# arduino.net
KiCad netlist of a schematic drawn in EAGLE
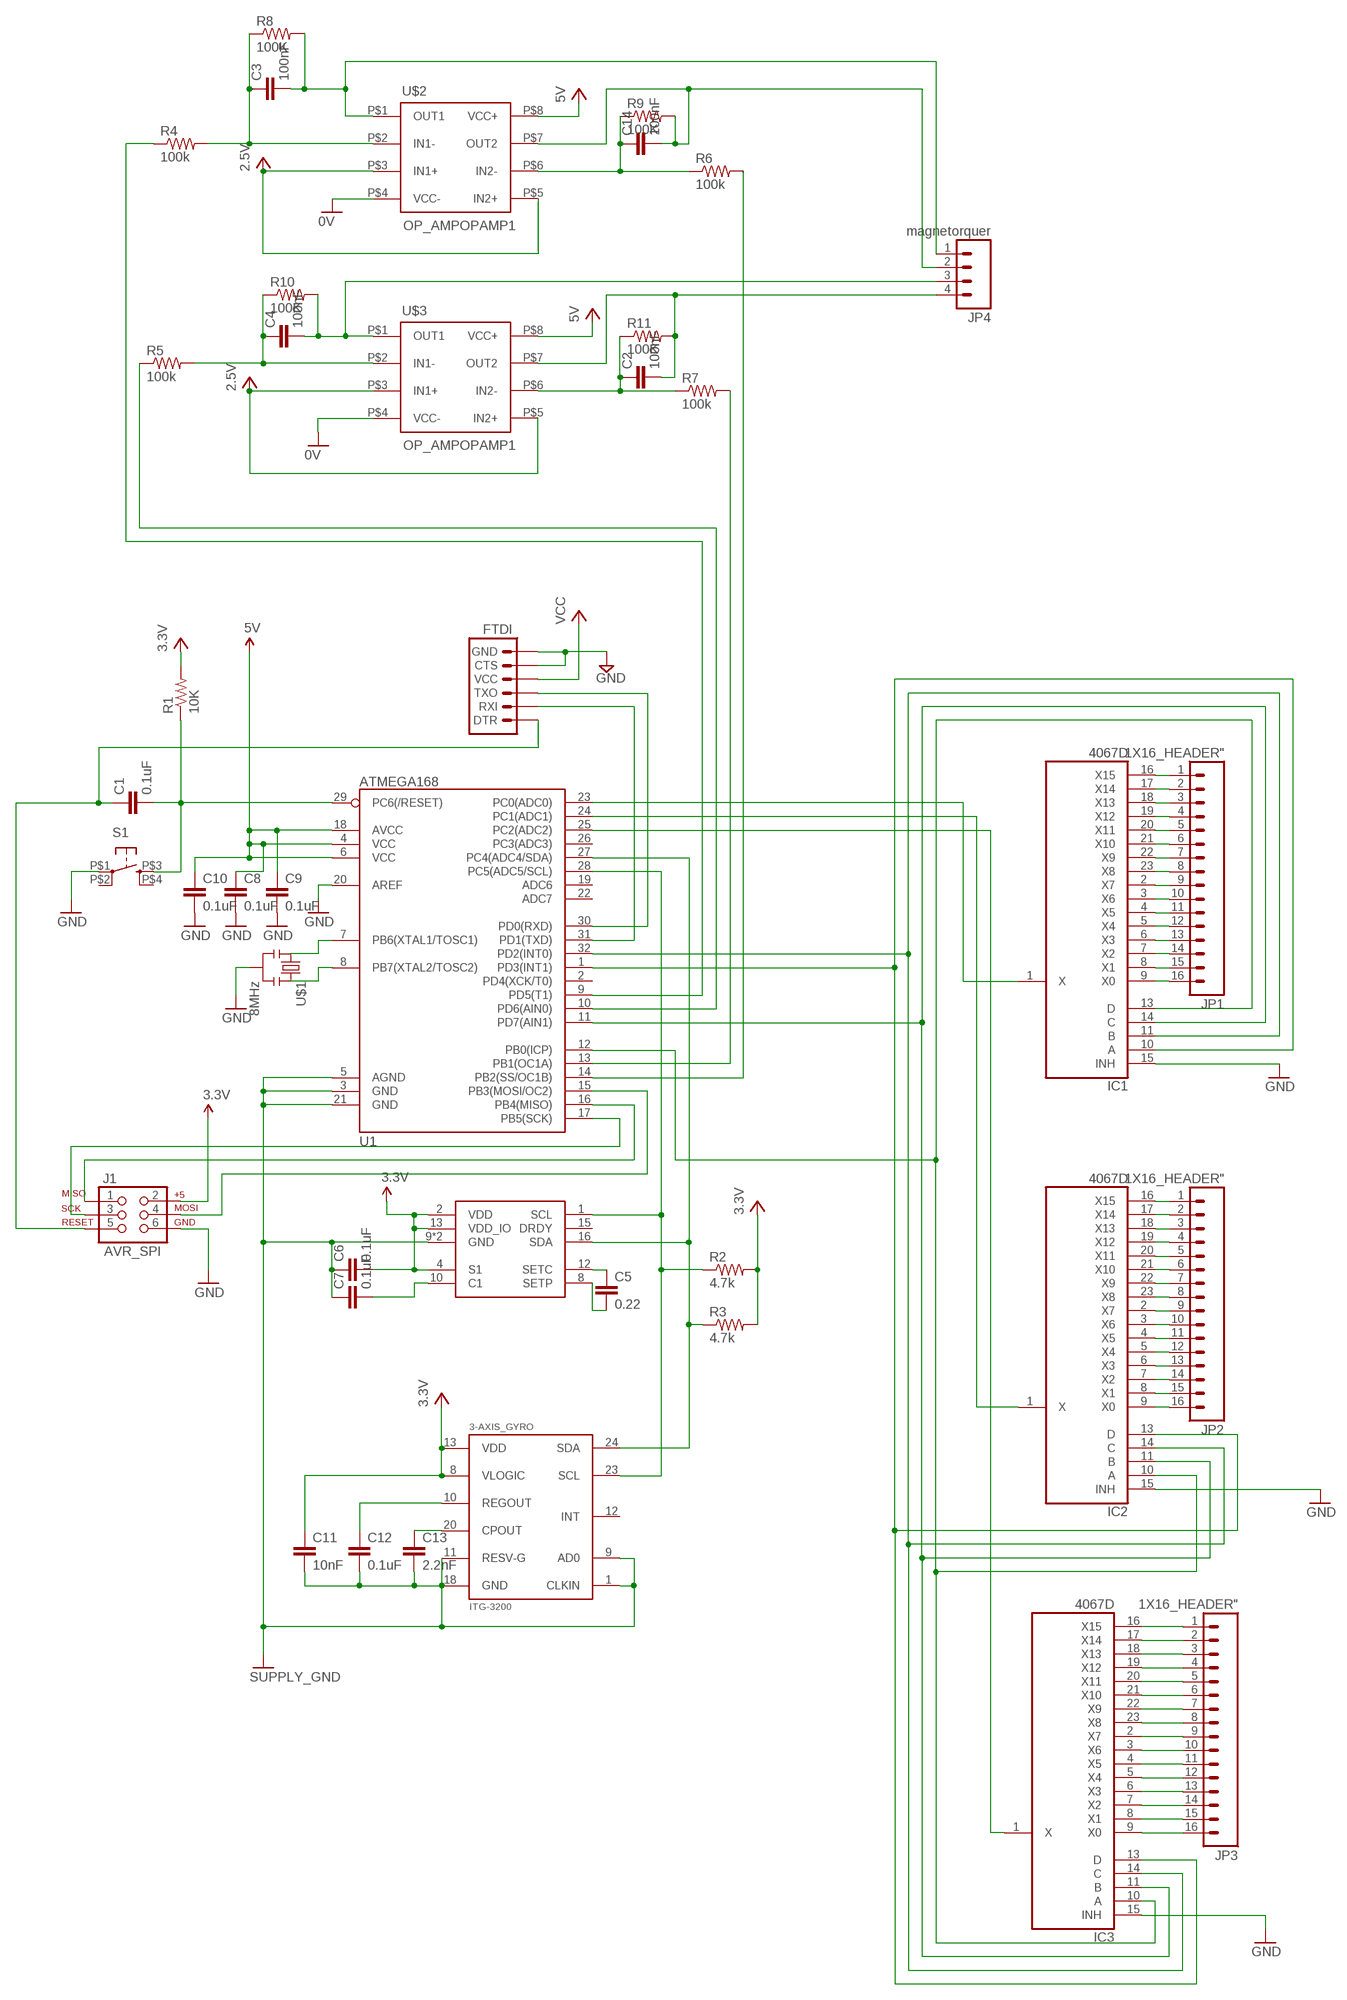
[diagram p0: schematic, sheet 1]

(export (version "E")
  (design (tool "Eeschema 10.0.6"))
  (components
    (comp (ref "3-AXIS_GYRO")
      (value "ITG-3200")
      (footprint "eagle-import:QFN-24")
      (libsource (lib "eagle-import") (part "ITG-3200"))
    )
    (comp (ref "3-AXIS_MAG")
      (value "HMC5883L")
      (footprint "eagle-import:LPCC16")
      (libsource (lib "eagle-import") (part "HMC5883L"))
    )
    (comp (ref "C1")
      (value "0.1uF")
      (footprint "eagle-import:0603-CAP")
      (libsource (lib "eagle-import") (part "CAP0603-CAP"))
    )
    (comp (ref "C2")
      (value "100nF")
      (footprint "eagle-import:0402-CAP")
      (libsource (lib "eagle-import") (part "CAP0402-CAP"))
    )
    (comp (ref "C3")
      (value "100nF")
      (footprint "eagle-import:0402-CAP")
      (libsource (lib "eagle-import") (part "CAP0402-CAP"))
    )
    (comp (ref "C4")
      (value "100nF")
      (footprint "eagle-import:0402-CAP")
      (libsource (lib "eagle-import") (part "CAP0402-CAP"))
    )
    (comp (ref "C5")
      (value "0.22")
      (footprint "eagle-import:0402-CAP")
      (libsource (lib "eagle-import") (part "CAP0402-CAP"))
    )
    (comp (ref "C6")
      (value "0.1uF")
      (footprint "eagle-import:0402-CAP")
      (libsource (lib "eagle-import") (part "CAP0402-CAP"))
    )
    (comp (ref "C7")
      (value "0.1uF")
      (footprint "eagle-import:0402-CAP")
      (libsource (lib "eagle-import") (part "CAP0402-CAP"))
    )
    (comp (ref "C8")
      (value "0.1uF")
      (footprint "eagle-import:0603-CAP")
      (libsource (lib "eagle-import") (part "CAP0603-CAP"))
    )
    (comp (ref "C9")
      (value "0.1uF")
      (footprint "eagle-import:0603-CAP")
      (libsource (lib "eagle-import") (part "CAP0603-CAP"))
    )
    (comp (ref "C10")
      (value "0.1uF")
      (footprint "eagle-import:0603-CAP")
      (libsource (lib "eagle-import") (part "CAP0603-CAP"))
    )
    (comp (ref "C11")
      (value "10nF")
      (footprint "eagle-import:0402-CAP")
      (libsource (lib "eagle-import") (part "CAP0402-CAP"))
    )
    (comp (ref "C12")
      (value "0.1uF")
      (footprint "eagle-import:0402-CAP")
      (libsource (lib "eagle-import") (part "CAP0402-CAP"))
    )
    (comp (ref "C13")
      (value "2.2nF")
      (footprint "eagle-import:0402-CAP")
      (libsource (lib "eagle-import") (part "CAP0402-CAP"))
    )
    (comp (ref "C14")
      (value "100nF")
      (footprint "eagle-import:0402-CAP")
      (libsource (lib "eagle-import") (part "CAP0402-CAP"))
    )
    (comp (ref "FTDI")
      (value "ARDUINO_SERIAL_PROGRAMPTH")
      (footprint "eagle-import:1X06")
      (libsource (lib "eagle-import") (part "ARDUINO_SERIAL_PROGRAMPTH"))
    )
    (comp (ref "IC1")
      (value "4067D")
      (footprint "eagle-import:SO24W")
      (libsource (lib "eagle-import") (part "4067D"))
    )
    (comp (ref "IC2")
      (value "4067D")
      (footprint "eagle-import:SO24W")
      (libsource (lib "eagle-import") (part "4067D"))
    )
    (comp (ref "IC3")
      (value "4067D")
      (footprint "eagle-import:SO24W")
      (libsource (lib "eagle-import") (part "4067D"))
    )
    (comp (ref "J1")
      (value "AVR_SPI")
      (footprint "eagle-import:2X3")
      (libsource (lib "eagle-import") (part "AVR_SPI_PRG_6PTH"))
    )
    (comp (ref "JP1")
      (value "1X16_HEADER\"")
      (footprint "eagle-import:1X16_HEADER")
      (libsource (lib "eagle-import") (part "1X16_HEADER{dblquote}"))
    )
    (comp (ref "JP2")
      (value "1X16_HEADER\"")
      (footprint "eagle-import:1X16_HEADER")
      (libsource (lib "eagle-import") (part "1X16_HEADER{dblquote}"))
    )
    (comp (ref "JP3")
      (value "1X16_HEADER\"")
      (footprint "eagle-import:1X16_HEADER")
      (libsource (lib "eagle-import") (part "1X16_HEADER{dblquote}"))
    )
    (comp (ref "JP4")
      (value "magnetorquer")
      (footprint "eagle-import:1X04_HEADER")
      (libsource (lib "eagle-import") (part "1X04_HEADER{dblquote}"))
    )
    (comp (ref "R1")
      (value "10K")
      (footprint "eagle-import:0805")
      (libsource (lib "eagle-import") (part "RESISTOR"))
    )
    (comp (ref "R2")
      (value "4.7k")
      (footprint "eagle-import:0805")
      (libsource (lib "eagle-import") (part "RESISTOR"))
    )
    (comp (ref "R3")
      (value "4.7k")
      (footprint "eagle-import:0805")
      (libsource (lib "eagle-import") (part "RESISTOR"))
    )
    (comp (ref "R4")
      (value "100k")
      (footprint "eagle-import:0805")
      (libsource (lib "eagle-import") (part "RESISTOR"))
    )
    (comp (ref "R5")
      (value "100k")
      (footprint "eagle-import:0805")
      (libsource (lib "eagle-import") (part "RESISTOR"))
    )
    (comp (ref "R6")
      (value "100k")
      (footprint "eagle-import:0805")
      (libsource (lib "eagle-import") (part "RESISTOR"))
    )
    (comp (ref "R7")
      (value "100k")
      (footprint "eagle-import:0805")
      (libsource (lib "eagle-import") (part "RESISTOR"))
    )
    (comp (ref "R8")
      (value "100K")
      (footprint "eagle-import:0805")
      (libsource (lib "eagle-import") (part "RESISTOR"))
    )
    (comp (ref "R9")
      (value "100K")
      (footprint "eagle-import:0805")
      (libsource (lib "eagle-import") (part "RESISTOR"))
    )
    (comp (ref "R10")
      (value "100K")
      (footprint "eagle-import:0805")
      (libsource (lib "eagle-import") (part "RESISTOR"))
    )
    (comp (ref "R11")
      (value "100K")
      (footprint "eagle-import:0805")
      (libsource (lib "eagle-import") (part "RESISTOR"))
    )
    (comp (ref "S1")
      (value "TAC_SWITCHKSA_SEALED")
      (footprint "eagle-import:KSA_SEALED_TAC_SWITCH")
      (libsource (lib "eagle-import") (part "TAC_SWITCHKSA_SEALED"))
    )
    (comp (ref "U$1")
      (value "8MHz")
      (footprint "eagle-import:RESONATOR")
      (libsource (lib "eagle-import") (part "RESONATOR{dblquote}"))
    )
    (comp (ref "U$2")
      (value "OP_AMPOPAMP1")
      (footprint "eagle-import:OPAMP")
      (libsource (lib "eagle-import") (part "OP_AMPOPAMP1"))
    )
    (comp (ref "U$3")
      (value "OP_AMPOPAMP1")
      (footprint "eagle-import:OPAMP")
      (libsource (lib "eagle-import") (part "OP_AMPOPAMP1"))
    )
    (comp (ref "U1")
      (value "ATMEGA168")
      (footprint "eagle-import:TQFP32-08")
      (libsource (lib "eagle-import") (part "ATMEGA168"))
    )
  )
  (nets
    (net (code "1") (name "0V") (class "Default")
      (node (ref "3-AXIS_GYRO") (pin "1") (pinfunction "CLKIN_1") (pintype "bidirectional"))
      (node (ref "3-AXIS_GYRO") (pin "11") (pinfunction "RESV-G_11") (pintype "bidirectional"))
      (node (ref "3-AXIS_GYRO") (pin "18") (pinfunction "GND_18") (pintype "bidirectional"))
      (node (ref "3-AXIS_GYRO") (pin "9") (pinfunction "AD0_9") (pintype "bidirectional"))
      (node (ref "3-AXIS_MAG") (pin "11") (pinfunction "GND_11") (pintype "bidirectional"))
      (node (ref "3-AXIS_MAG") (pin "9") (pinfunction "GND_9") (pintype "bidirectional"))
      (node (ref "C10") (pin "2") (pinfunction "2_2") (pintype "passive"))
      (node (ref "C11") (pin "2") (pinfunction "2_2") (pintype "passive"))
      (node (ref "C12") (pin "2") (pinfunction "2_2") (pintype "passive"))
      (node (ref "C13") (pin "2") (pinfunction "2_2") (pintype "passive"))
      (node (ref "C6") (pin "1") (pinfunction "1_1") (pintype "passive"))
      (node (ref "C7") (pin "1") (pinfunction "1_1") (pintype "passive"))
      (node (ref "C8") (pin "2") (pinfunction "2_2") (pintype "passive"))
      (node (ref "C9") (pin "2") (pinfunction "2_2") (pintype "passive"))
      (node (ref "FTDI") (pin "5") (pinfunction "CTS_5") (pintype "passive"))
      (node (ref "FTDI") (pin "6") (pinfunction "GND_6") (pintype "passive"))
      (node (ref "IC1") (pin "15") (pinfunction "INH_15") (pintype "input"))
      (node (ref "IC2") (pin "15") (pinfunction "INH_15") (pintype "input"))
      (node (ref "IC3") (pin "15") (pinfunction "INH_15") (pintype "input"))
      (node (ref "J1") (pin "6") (pinfunction "6_6") (pintype "passive"))
      (node (ref "S1") (pin "P$1") (pinfunction "1_P$1") (pintype "passive"))
      (node (ref "U$1") (pin "2") (pinfunction "2_2") (pintype "passive"))
      (node (ref "U$2") (pin "P$4") (pinfunction "VCC-_P$4") (pintype "bidirectional"))
      (node (ref "U$3") (pin "P$4") (pinfunction "VCC-_P$4") (pintype "bidirectional"))
      (node (ref "U1") (pin "20") (pinfunction "AREF_20") (pintype "bidirectional"))
      (node (ref "U1") (pin "21") (pinfunction "GND_21") (pintype "bidirectional"))
      (node (ref "U1") (pin "3") (pinfunction "GND_3") (pintype "bidirectional"))
      (node (ref "U1") (pin "5") (pinfunction "AGND_5") (pintype "bidirectional"))
    )
    (net (code "2") (name "2.5V") (class "Default")
      (node (ref "3-AXIS_GYRO") (pin "13") (pinfunction "VDD_13") (pintype "bidirectional"))
      (node (ref "3-AXIS_GYRO") (pin "8") (pinfunction "VLOGIC_8") (pintype "bidirectional"))
      (node (ref "3-AXIS_MAG") (pin "13") (pinfunction "VDD_IO_13") (pintype "power_in"))
      (node (ref "3-AXIS_MAG") (pin "2") (pinfunction "VDD_2") (pintype "power_in"))
      (node (ref "3-AXIS_MAG") (pin "4") (pinfunction "S1_4") (pintype "power_in"))
      (node (ref "C10") (pin "1") (pinfunction "1_1") (pintype "passive"))
      (node (ref "C11") (pin "1") (pinfunction "1_1") (pintype "passive"))
      (node (ref "C6") (pin "2") (pinfunction "2_2") (pintype "passive"))
      (node (ref "C8") (pin "1") (pinfunction "1_1") (pintype "passive"))
      (node (ref "C9") (pin "1") (pinfunction "1_1") (pintype "passive"))
      (node (ref "FTDI") (pin "4") (pinfunction "VCC_4") (pintype "passive"))
      (node (ref "J1") (pin "2") (pinfunction "2_2") (pintype "passive"))
      (node (ref "R1") (pin "2") (pinfunction "2_2") (pintype "passive"))
      (node (ref "R2") (pin "2") (pinfunction "2_2") (pintype "passive"))
      (node (ref "R3") (pin "2") (pinfunction "2_2") (pintype "passive"))
      (node (ref "U$2") (pin "P$3") (pinfunction "IN1+_P$3") (pintype "bidirectional"))
      (node (ref "U$2") (pin "P$5") (pinfunction "IN2+_P$5") (pintype "bidirectional"))
      (node (ref "U$2") (pin "P$8") (pinfunction "VCC+_P$8") (pintype "bidirectional"))
      (node (ref "U$3") (pin "P$3") (pinfunction "IN1+_P$3") (pintype "bidirectional"))
      (node (ref "U$3") (pin "P$5") (pinfunction "IN2+_P$5") (pintype "bidirectional"))
      (node (ref "U$3") (pin "P$8") (pinfunction "VCC+_P$8") (pintype "bidirectional"))
      (node (ref "U1") (pin "18") (pinfunction "AVCC_18") (pintype "bidirectional"))
      (node (ref "U1") (pin "4") (pinfunction "VCC_4") (pintype "bidirectional"))
      (node (ref "U1") (pin "6") (pinfunction "VCC_6") (pintype "bidirectional"))
    )
    (net (code "3") (name "Net-(3-AXIS_GYRO-CPOUT)") (class "Default")
      (node (ref "3-AXIS_GYRO") (pin "20") (pinfunction "CPOUT_20") (pintype "bidirectional"))
      (node (ref "C13") (pin "1") (pinfunction "1_1") (pintype "passive"))
    )
    (net (code "4") (name "Net-(3-AXIS_GYRO-REGOUT)") (class "Default")
      (node (ref "3-AXIS_GYRO") (pin "10") (pinfunction "REGOUT_10") (pintype "bidirectional"))
      (node (ref "C12") (pin "1") (pinfunction "1_1") (pintype "passive"))
    )
    (net (code "5") (name "Net-(3-AXIS_GYRO-SCL)") (class "Default")
      (node (ref "3-AXIS_GYRO") (pin "23") (pinfunction "SCL_23") (pintype "bidirectional"))
      (node (ref "3-AXIS_MAG") (pin "1") (pinfunction "SCL_1") (pintype "input"))
      (node (ref "R2") (pin "1") (pinfunction "1_1") (pintype "passive"))
      (node (ref "U1") (pin "28") (pinfunction "PC5(ADC5/SCL)_28") (pintype "bidirectional"))
    )
    (net (code "6") (name "Net-(3-AXIS_GYRO-SDA)") (class "Default")
      (node (ref "3-AXIS_GYRO") (pin "24") (pinfunction "SDA_24") (pintype "bidirectional"))
      (node (ref "3-AXIS_MAG") (pin "16") (pinfunction "SDA_16") (pintype "input"))
      (node (ref "R3") (pin "1") (pinfunction "1_1") (pintype "passive"))
      (node (ref "U1") (pin "27") (pinfunction "PC4(ADC4/SDA)_27") (pintype "bidirectional"))
    )
    (net (code "7") (name "Net-(3-AXIS_MAG-C1)") (class "Default")
      (node (ref "3-AXIS_MAG") (pin "10") (pinfunction "C1_10") (pintype "passive"))
      (node (ref "C7") (pin "2") (pinfunction "2_2") (pintype "passive"))
    )
    (net (code "8") (name "Net-(3-AXIS_MAG-SETC)") (class "Default")
      (node (ref "3-AXIS_MAG") (pin "12") (pinfunction "SETC_12") (pintype "passive"))
      (node (ref "C5") (pin "1") (pinfunction "1_1") (pintype "passive"))
    )
    (net (code "9") (name "Net-(3-AXIS_MAG-SETP)") (class "Default")
      (node (ref "3-AXIS_MAG") (pin "8") (pinfunction "SETP_8") (pintype "passive"))
      (node (ref "C5") (pin "2") (pinfunction "2_2") (pintype "passive"))
    )
    (net (code "10") (name "Net-(FTDI-DTR)") (class "Default")
      (node (ref "C1") (pin "1") (pinfunction "1_1") (pintype "passive"))
      (node (ref "FTDI") (pin "1") (pinfunction "DTR_1") (pintype "passive"))
      (node (ref "J1") (pin "5") (pinfunction "5_5") (pintype "passive"))
    )
    (net (code "11") (name "Net-(FTDI-RXI)") (class "Default")
      (node (ref "FTDI") (pin "2") (pinfunction "RXI_2") (pintype "passive"))
      (node (ref "U1") (pin "31") (pinfunction "PD1(TXD)_31") (pintype "bidirectional"))
    )
    (net (code "12") (name "Net-(FTDI-TXO)") (class "Default")
      (node (ref "FTDI") (pin "3") (pinfunction "TXO_3") (pintype "passive"))
      (node (ref "U1") (pin "30") (pinfunction "PD0(RXD)_30") (pintype "bidirectional"))
    )
    (net (code "13") (name "Net-(IC1A-A)") (class "Default")
      (node (ref "IC1") (pin "10") (pinfunction "A_10") (pintype "input"))
      (node (ref "IC2") (pin "13") (pinfunction "D_13") (pintype "input"))
      (node (ref "IC3") (pin "13") (pinfunction "D_13") (pintype "input"))
      (node (ref "U1") (pin "1") (pinfunction "PD3(INT1)_1") (pintype "bidirectional"))
    )
    (net (code "14") (name "Net-(IC1A-B)") (class "Default")
      (node (ref "IC1") (pin "11") (pinfunction "B_11") (pintype "input"))
      (node (ref "IC2") (pin "14") (pinfunction "C_14") (pintype "input"))
      (node (ref "IC3") (pin "14") (pinfunction "C_14") (pintype "input"))
      (node (ref "U1") (pin "32") (pinfunction "PD2(INT0)_32") (pintype "bidirectional"))
    )
    (net (code "15") (name "Net-(IC1A-C)") (class "Default")
      (node (ref "IC1") (pin "14") (pinfunction "C_14") (pintype "input"))
      (node (ref "IC2") (pin "11") (pinfunction "B_11") (pintype "input"))
      (node (ref "IC3") (pin "11") (pinfunction "B_11") (pintype "input"))
      (node (ref "U1") (pin "11") (pinfunction "PD7(AIN1)_11") (pintype "bidirectional"))
    )
    (net (code "16") (name "Net-(IC1A-D)") (class "Default")
      (node (ref "IC1") (pin "13") (pinfunction "D_13") (pintype "input"))
      (node (ref "IC2") (pin "10") (pinfunction "A_10") (pintype "input"))
      (node (ref "IC3") (pin "10") (pinfunction "A_10") (pintype "input"))
      (node (ref "U1") (pin "12") (pinfunction "PB0(ICP)_12") (pintype "bidirectional"))
    )
    (net (code "17") (name "Net-(IC1A-X)") (class "Default")
      (node (ref "IC1") (pin "1") (pinfunction "X_1") (pintype "output"))
      (node (ref "U1") (pin "23") (pinfunction "PC0(ADC0)_23") (pintype "bidirectional"))
    )
    (net (code "18") (name "Net-(IC1A-X0)") (class "Default")
      (node (ref "IC1") (pin "9") (pinfunction "X0_9") (pintype "input"))
      (node (ref "JP1") (pin "16") (pinfunction "16_16") (pintype "passive"))
    )
    (net (code "19") (name "Net-(IC1A-X1)") (class "Default")
      (node (ref "IC1") (pin "8") (pinfunction "X1_8") (pintype "input"))
      (node (ref "JP1") (pin "15") (pinfunction "15_15") (pintype "passive"))
    )
    (net (code "20") (name "Net-(IC1A-X2)") (class "Default")
      (node (ref "IC1") (pin "7") (pinfunction "X2_7") (pintype "input"))
      (node (ref "JP1") (pin "14") (pinfunction "14_14") (pintype "passive"))
    )
    (net (code "21") (name "Net-(IC1A-X3)") (class "Default")
      (node (ref "IC1") (pin "6") (pinfunction "X3_6") (pintype "input"))
      (node (ref "JP1") (pin "13") (pinfunction "13_13") (pintype "passive"))
    )
    (net (code "22") (name "Net-(IC1A-X4)") (class "Default")
      (node (ref "IC1") (pin "5") (pinfunction "X4_5") (pintype "input"))
      (node (ref "JP1") (pin "12") (pinfunction "12_12") (pintype "passive"))
    )
    (net (code "23") (name "Net-(IC1A-X5)") (class "Default")
      (node (ref "IC1") (pin "4") (pinfunction "X5_4") (pintype "input"))
      (node (ref "JP1") (pin "11") (pinfunction "11_11") (pintype "passive"))
    )
    (net (code "24") (name "Net-(IC1A-X6)") (class "Default")
      (node (ref "IC1") (pin "3") (pinfunction "X6_3") (pintype "input"))
      (node (ref "JP1") (pin "10") (pinfunction "10_10") (pintype "passive"))
    )
    (net (code "25") (name "Net-(IC1A-X7)") (class "Default")
      (node (ref "IC1") (pin "2") (pinfunction "X7_2") (pintype "input"))
      (node (ref "JP1") (pin "9") (pinfunction "9_9") (pintype "passive"))
    )
    (net (code "26") (name "Net-(IC1A-X8)") (class "Default")
      (node (ref "IC1") (pin "23") (pinfunction "X8_23") (pintype "input"))
      (node (ref "JP1") (pin "8") (pinfunction "8_8") (pintype "passive"))
    )
    (net (code "27") (name "Net-(IC1A-X9)") (class "Default")
      (node (ref "IC1") (pin "22") (pinfunction "X9_22") (pintype "input"))
      (node (ref "JP1") (pin "7") (pinfunction "7_7") (pintype "passive"))
    )
    (net (code "28") (name "Net-(IC1A-X10)") (class "Default")
      (node (ref "IC1") (pin "21") (pinfunction "X10_21") (pintype "input"))
      (node (ref "JP1") (pin "6") (pinfunction "6_6") (pintype "passive"))
    )
    (net (code "29") (name "Net-(IC1A-X11)") (class "Default")
      (node (ref "IC1") (pin "20") (pinfunction "X11_20") (pintype "input"))
      (node (ref "JP1") (pin "5") (pinfunction "5_5") (pintype "passive"))
    )
    (net (code "30") (name "Net-(IC1A-X12)") (class "Default")
      (node (ref "IC1") (pin "19") (pinfunction "X12_19") (pintype "input"))
      (node (ref "JP1") (pin "4") (pinfunction "4_4") (pintype "passive"))
    )
    (net (code "31") (name "Net-(IC1A-X13)") (class "Default")
      (node (ref "IC1") (pin "18") (pinfunction "X13_18") (pintype "input"))
      (node (ref "JP1") (pin "3") (pinfunction "3_3") (pintype "passive"))
    )
    (net (code "32") (name "Net-(IC1A-X14)") (class "Default")
      (node (ref "IC1") (pin "17") (pinfunction "X14_17") (pintype "input"))
      (node (ref "JP1") (pin "2") (pinfunction "2_2") (pintype "passive"))
    )
    (net (code "33") (name "Net-(IC1A-X15)") (class "Default")
      (node (ref "IC1") (pin "16") (pinfunction "X15_16") (pintype "input"))
      (node (ref "JP1") (pin "1") (pinfunction "1_1") (pintype "passive"))
    )
    (net (code "34") (name "Net-(IC2A-X)") (class "Default")
      (node (ref "IC2") (pin "1") (pinfunction "X_1") (pintype "output"))
      (node (ref "U1") (pin "24") (pinfunction "PC1(ADC1)_24") (pintype "bidirectional"))
    )
    (net (code "35") (name "Net-(IC2A-X0)") (class "Default")
      (node (ref "IC2") (pin "9") (pinfunction "X0_9") (pintype "input"))
      (node (ref "JP2") (pin "16") (pinfunction "16_16") (pintype "passive"))
    )
    (net (code "36") (name "Net-(IC2A-X1)") (class "Default")
      (node (ref "IC2") (pin "8") (pinfunction "X1_8") (pintype "input"))
      (node (ref "JP2") (pin "15") (pinfunction "15_15") (pintype "passive"))
    )
    (net (code "37") (name "Net-(IC2A-X2)") (class "Default")
      (node (ref "IC2") (pin "7") (pinfunction "X2_7") (pintype "input"))
      (node (ref "JP2") (pin "14") (pinfunction "14_14") (pintype "passive"))
    )
    (net (code "38") (name "Net-(IC2A-X3)") (class "Default")
      (node (ref "IC2") (pin "6") (pinfunction "X3_6") (pintype "input"))
      (node (ref "JP2") (pin "13") (pinfunction "13_13") (pintype "passive"))
    )
    (net (code "39") (name "Net-(IC2A-X4)") (class "Default")
      (node (ref "IC2") (pin "5") (pinfunction "X4_5") (pintype "input"))
      (node (ref "JP2") (pin "12") (pinfunction "12_12") (pintype "passive"))
    )
    (net (code "40") (name "Net-(IC2A-X5)") (class "Default")
      (node (ref "IC2") (pin "4") (pinfunction "X5_4") (pintype "input"))
      (node (ref "JP2") (pin "11") (pinfunction "11_11") (pintype "passive"))
    )
    (net (code "41") (name "Net-(IC2A-X6)") (class "Default")
      (node (ref "IC2") (pin "3") (pinfunction "X6_3") (pintype "input"))
      (node (ref "JP2") (pin "10") (pinfunction "10_10") (pintype "passive"))
    )
    (net (code "42") (name "Net-(IC2A-X7)") (class "Default")
      (node (ref "IC2") (pin "2") (pinfunction "X7_2") (pintype "input"))
      (node (ref "JP2") (pin "9") (pinfunction "9_9") (pintype "passive"))
    )
    (net (code "43") (name "Net-(IC2A-X8)") (class "Default")
      (node (ref "IC2") (pin "23") (pinfunction "X8_23") (pintype "input"))
      (node (ref "JP2") (pin "8") (pinfunction "8_8") (pintype "passive"))
    )
    (net (code "44") (name "Net-(IC2A-X9)") (class "Default")
      (node (ref "IC2") (pin "22") (pinfunction "X9_22") (pintype "input"))
      (node (ref "JP2") (pin "7") (pinfunction "7_7") (pintype "passive"))
    )
    (net (code "45") (name "Net-(IC2A-X10)") (class "Default")
      (node (ref "IC2") (pin "21") (pinfunction "X10_21") (pintype "input"))
      (node (ref "JP2") (pin "6") (pinfunction "6_6") (pintype "passive"))
    )
    (net (code "46") (name "Net-(IC2A-X11)") (class "Default")
      (node (ref "IC2") (pin "20") (pinfunction "X11_20") (pintype "input"))
      (node (ref "JP2") (pin "5") (pinfunction "5_5") (pintype "passive"))
    )
    (net (code "47") (name "Net-(IC2A-X12)") (class "Default")
      (node (ref "IC2") (pin "19") (pinfunction "X12_19") (pintype "input"))
      (node (ref "JP2") (pin "4") (pinfunction "4_4") (pintype "passive"))
    )
    (net (code "48") (name "Net-(IC2A-X13)") (class "Default")
      (node (ref "IC2") (pin "18") (pinfunction "X13_18") (pintype "input"))
      (node (ref "JP2") (pin "3") (pinfunction "3_3") (pintype "passive"))
    )
    (net (code "49") (name "Net-(IC2A-X14)") (class "Default")
      (node (ref "IC2") (pin "17") (pinfunction "X14_17") (pintype "input"))
      (node (ref "JP2") (pin "2") (pinfunction "2_2") (pintype "passive"))
    )
    (net (code "50") (name "Net-(IC2A-X15)") (class "Default")
      (node (ref "IC2") (pin "16") (pinfunction "X15_16") (pintype "input"))
      (node (ref "JP2") (pin "1") (pinfunction "1_1") (pintype "passive"))
    )
    (net (code "51") (name "Net-(IC3A-X)") (class "Default")
      (node (ref "IC3") (pin "1") (pinfunction "X_1") (pintype "output"))
      (node (ref "U1") (pin "25") (pinfunction "PC2(ADC2)_25") (pintype "bidirectional"))
    )
    (net (code "52") (name "Net-(IC3A-X0)") (class "Default")
      (node (ref "IC3") (pin "9") (pinfunction "X0_9") (pintype "input"))
      (node (ref "JP3") (pin "16") (pinfunction "16_16") (pintype "passive"))
    )
    (net (code "53") (name "Net-(IC3A-X1)") (class "Default")
      (node (ref "IC3") (pin "8") (pinfunction "X1_8") (pintype "input"))
      (node (ref "JP3") (pin "15") (pinfunction "15_15") (pintype "passive"))
    )
    (net (code "54") (name "Net-(IC3A-X2)") (class "Default")
      (node (ref "IC3") (pin "7") (pinfunction "X2_7") (pintype "input"))
      (node (ref "JP3") (pin "14") (pinfunction "14_14") (pintype "passive"))
    )
    (net (code "55") (name "Net-(IC3A-X3)") (class "Default")
      (node (ref "IC3") (pin "6") (pinfunction "X3_6") (pintype "input"))
      (node (ref "JP3") (pin "13") (pinfunction "13_13") (pintype "passive"))
    )
    (net (code "56") (name "Net-(IC3A-X4)") (class "Default")
      (node (ref "IC3") (pin "5") (pinfunction "X4_5") (pintype "input"))
      (node (ref "JP3") (pin "12") (pinfunction "12_12") (pintype "passive"))
    )
    (net (code "57") (name "Net-(IC3A-X5)") (class "Default")
      (node (ref "IC3") (pin "4") (pinfunction "X5_4") (pintype "input"))
      (node (ref "JP3") (pin "11") (pinfunction "11_11") (pintype "passive"))
    )
    (net (code "58") (name "Net-(IC3A-X6)") (class "Default")
      (node (ref "IC3") (pin "3") (pinfunction "X6_3") (pintype "input"))
      (node (ref "JP3") (pin "10") (pinfunction "10_10") (pintype "passive"))
    )
    (net (code "59") (name "Net-(IC3A-X7)") (class "Default")
      (node (ref "IC3") (pin "2") (pinfunction "X7_2") (pintype "input"))
      (node (ref "JP3") (pin "9") (pinfunction "9_9") (pintype "passive"))
    )
    (net (code "60") (name "Net-(IC3A-X8)") (class "Default")
      (node (ref "IC3") (pin "23") (pinfunction "X8_23") (pintype "input"))
      (node (ref "JP3") (pin "8") (pinfunction "8_8") (pintype "passive"))
    )
    (net (code "61") (name "Net-(IC3A-X9)") (class "Default")
      (node (ref "IC3") (pin "22") (pinfunction "X9_22") (pintype "input"))
      (node (ref "JP3") (pin "7") (pinfunction "7_7") (pintype "passive"))
    )
    (net (code "62") (name "Net-(IC3A-X10)") (class "Default")
      (node (ref "IC3") (pin "21") (pinfunction "X10_21") (pintype "input"))
      (node (ref "JP3") (pin "6") (pinfunction "6_6") (pintype "passive"))
    )
    (net (code "63") (name "Net-(IC3A-X11)") (class "Default")
      (node (ref "IC3") (pin "20") (pinfunction "X11_20") (pintype "input"))
      (node (ref "JP3") (pin "5") (pinfunction "5_5") (pintype "passive"))
    )
    (net (code "64") (name "Net-(IC3A-X12)") (class "Default")
      (node (ref "IC3") (pin "19") (pinfunction "X12_19") (pintype "input"))
      (node (ref "JP3") (pin "4") (pinfunction "4_4") (pintype "passive"))
    )
    (net (code "65") (name "Net-(IC3A-X13)") (class "Default")
      (node (ref "IC3") (pin "18") (pinfunction "X13_18") (pintype "input"))
      (node (ref "JP3") (pin "3") (pinfunction "3_3") (pintype "passive"))
    )
    (net (code "66") (name "Net-(IC3A-X14)") (class "Default")
      (node (ref "IC3") (pin "17") (pinfunction "X14_17") (pintype "input"))
      (node (ref "JP3") (pin "2") (pinfunction "2_2") (pintype "passive"))
    )
    (net (code "67") (name "Net-(IC3A-X15)") (class "Default")
      (node (ref "IC3") (pin "16") (pinfunction "X15_16") (pintype "input"))
      (node (ref "JP3") (pin "1") (pinfunction "1_1") (pintype "passive"))
    )
    (net (code "68") (name "Net-(S1-3)") (class "Default")
      (node (ref "C1") (pin "2") (pinfunction "2_2") (pintype "passive"))
      (node (ref "R1") (pin "1") (pinfunction "1_1") (pintype "passive"))
      (node (ref "S1") (pin "P$3") (pinfunction "3_P$3") (pintype "passive"))
      (node (ref "U1") (pin "29") (pinfunction "PC6(/RESET)_29") (pintype "bidirectional"))
    )
    (net (code "69") (name "Net-(U$2-IN1-)") (class "Default")
      (node (ref "C3") (pin "1") (pinfunction "1_1") (pintype "passive"))
      (node (ref "R4") (pin "2") (pinfunction "2_2") (pintype "passive"))
      (node (ref "R8") (pin "1") (pinfunction "1_1") (pintype "passive"))
      (node (ref "U$2") (pin "P$2") (pinfunction "IN1-_P$2") (pintype "bidirectional"))
    )
    (net (code "70") (name "Net-(U$2-IN2-)") (class "Default")
      (node (ref "C14") (pin "1") (pinfunction "1_1") (pintype "passive"))
      (node (ref "R6") (pin "1") (pinfunction "1_1") (pintype "passive"))
      (node (ref "R9") (pin "1") (pinfunction "1_1") (pintype "passive"))
      (node (ref "U$2") (pin "P$6") (pinfunction "IN2-_P$6") (pintype "bidirectional"))
    )
    (net (code "71") (name "Net-(U$2-OUT1)") (class "Default")
      (node (ref "C3") (pin "2") (pinfunction "2_2") (pintype "passive"))
      (node (ref "JP4") (pin "1") (pinfunction "1_1") (pintype "passive"))
      (node (ref "R8") (pin "2") (pinfunction "2_2") (pintype "passive"))
      (node (ref "U$2") (pin "P$1") (pinfunction "OUT1_P$1") (pintype "bidirectional"))
    )
    (net (code "72") (name "Net-(U$2-OUT2)") (class "Default")
      (node (ref "C14") (pin "2") (pinfunction "2_2") (pintype "passive"))
      (node (ref "JP4") (pin "2") (pinfunction "2_2") (pintype "passive"))
      (node (ref "R9") (pin "2") (pinfunction "2_2") (pintype "passive"))
      (node (ref "U$2") (pin "P$7") (pinfunction "OUT2_P$7") (pintype "bidirectional"))
    )
    (net (code "73") (name "Net-(U$3-IN1-)") (class "Default")
      (node (ref "C4") (pin "1") (pinfunction "1_1") (pintype "passive"))
      (node (ref "R10") (pin "1") (pinfunction "1_1") (pintype "passive"))
      (node (ref "R5") (pin "2") (pinfunction "2_2") (pintype "passive"))
      (node (ref "U$3") (pin "P$2") (pinfunction "IN1-_P$2") (pintype "bidirectional"))
    )
    (net (code "74") (name "Net-(U$3-IN2-)") (class "Default")
      (node (ref "C2") (pin "1") (pinfunction "1_1") (pintype "passive"))
      (node (ref "R11") (pin "1") (pinfunction "1_1") (pintype "passive"))
      (node (ref "R7") (pin "1") (pinfunction "1_1") (pintype "passive"))
      (node (ref "U$3") (pin "P$6") (pinfunction "IN2-_P$6") (pintype "bidirectional"))
    )
    (net (code "75") (name "Net-(U$3-OUT1)") (class "Default")
      (node (ref "C4") (pin "2") (pinfunction "2_2") (pintype "passive"))
      (node (ref "JP4") (pin "3") (pinfunction "3_3") (pintype "passive"))
      (node (ref "R10") (pin "2") (pinfunction "2_2") (pintype "passive"))
      (node (ref "U$3") (pin "P$1") (pinfunction "OUT1_P$1") (pintype "bidirectional"))
    )
    (net (code "76") (name "Net-(U$3-OUT2)") (class "Default")
      (node (ref "C2") (pin "2") (pinfunction "2_2") (pintype "passive"))
      (node (ref "JP4") (pin "4") (pinfunction "4_4") (pintype "passive"))
      (node (ref "R11") (pin "2") (pinfunction "2_2") (pintype "passive"))
      (node (ref "U$3") (pin "P$7") (pinfunction "OUT2_P$7") (pintype "bidirectional"))
    )
    (net (code "77") (name "Net-(U1-PB1(OC1A))") (class "Default")
      (node (ref "R7") (pin "2") (pinfunction "2_2") (pintype "passive"))
      (node (ref "U1") (pin "13") (pinfunction "PB1(OC1A)_13") (pintype "bidirectional"))
    )
    (net (code "78") (name "Net-(U1-PB2(SS{slash}OC1B))") (class "Default")
      (node (ref "R6") (pin "2") (pinfunction "2_2") (pintype "passive"))
      (node (ref "U1") (pin "14") (pinfunction "PB2(SS/OC1B)_14") (pintype "bidirectional"))
    )
    (net (code "79") (name "Net-(U1-PB3(MOSI{slash}OC2))") (class "Default")
      (node (ref "J1") (pin "4") (pinfunction "4_4") (pintype "passive"))
      (node (ref "U1") (pin "15") (pinfunction "PB3(MOSI/OC2)_15") (pintype "bidirectional"))
    )
    (net (code "80") (name "Net-(U1-PB4(MISO))") (class "Default")
      (node (ref "J1") (pin "1") (pinfunction "1_1") (pintype "passive"))
      (node (ref "U1") (pin "16") (pinfunction "PB4(MISO)_16") (pintype "bidirectional"))
    )
    (net (code "81") (name "Net-(U1-PB5(SCK))") (class "Default")
      (node (ref "J1") (pin "3") (pinfunction "3_3") (pintype "passive"))
      (node (ref "U1") (pin "17") (pinfunction "PB5(SCK)_17") (pintype "bidirectional"))
    )
    (net (code "82") (name "Net-(U1-PB6(XTAL1{slash}TOSC1))") (class "Default")
      (node (ref "U$1") (pin "1") (pinfunction "1_1") (pintype "passive"))
      (node (ref "U1") (pin "7") (pinfunction "PB6(XTAL1/TOSC1)_7") (pintype "bidirectional"))
    )
    (net (code "83") (name "Net-(U1-PB7(XTAL2{slash}TOSC2))") (class "Default")
      (node (ref "U$1") (pin "3") (pinfunction "3_3") (pintype "passive"))
      (node (ref "U1") (pin "8") (pinfunction "PB7(XTAL2/TOSC2)_8") (pintype "bidirectional"))
    )
    (net (code "84") (name "Net-(U1-PD5(T1))") (class "Default")
      (node (ref "R4") (pin "1") (pinfunction "1_1") (pintype "passive"))
      (node (ref "U1") (pin "9") (pinfunction "PD5(T1)_9") (pintype "bidirectional"))
    )
    (net (code "85") (name "Net-(U1-PD6(AIN0))") (class "Default")
      (node (ref "R5") (pin "1") (pinfunction "1_1") (pintype "passive"))
      (node (ref "U1") (pin "10") (pinfunction "PD6(AIN0)_10") (pintype "bidirectional"))
    )
    (net (code "86") (name "unconnected-(3-AXIS_GYRO-INT-Pad12)") (class "Default")
      (node (ref "3-AXIS_GYRO") (pin "12") (pinfunction "INT_12") (pintype "bidirectional"))
    )
    (net (code "87") (name "unconnected-(3-AXIS_MAG-DRDY-Pad15)") (class "Default")
      (node (ref "3-AXIS_MAG") (pin "15") (pinfunction "DRDY_15") (pintype "input"))
    )
    (net (code "88") (name "unconnected-(S1-2-PadP$2)") (class "Default")
      (node (ref "S1") (pin "P$2") (pinfunction "2_P$2") (pintype "passive"))
    )
    (net (code "89") (name "unconnected-(S1-4-PadP$4)") (class "Default")
      (node (ref "S1") (pin "P$4") (pinfunction "4_P$4") (pintype "passive"))
    )
    (net (code "90") (name "unconnected-(U1-ADC6-Pad19)") (class "Default")
      (node (ref "U1") (pin "19") (pinfunction "ADC6_19") (pintype "bidirectional"))
    )
    (net (code "91") (name "unconnected-(U1-ADC7-Pad22)") (class "Default")
      (node (ref "U1") (pin "22") (pinfunction "ADC7_22") (pintype "bidirectional"))
    )
    (net (code "92") (name "unconnected-(U1-PC3(ADC3)-Pad26)") (class "Default")
      (node (ref "U1") (pin "26") (pinfunction "PC3(ADC3)_26") (pintype "bidirectional"))
    )
    (net (code "93") (name "unconnected-(U1-PD4(XCK{slash}T0)-Pad2)") (class "Default")
      (node (ref "U1") (pin "2") (pinfunction "PD4(XCK/T0)_2") (pintype "bidirectional"))
    )
  )
)
